# LTE_GPS_Power.net
KiCad netlist of a schematic drawn in Altium Designer
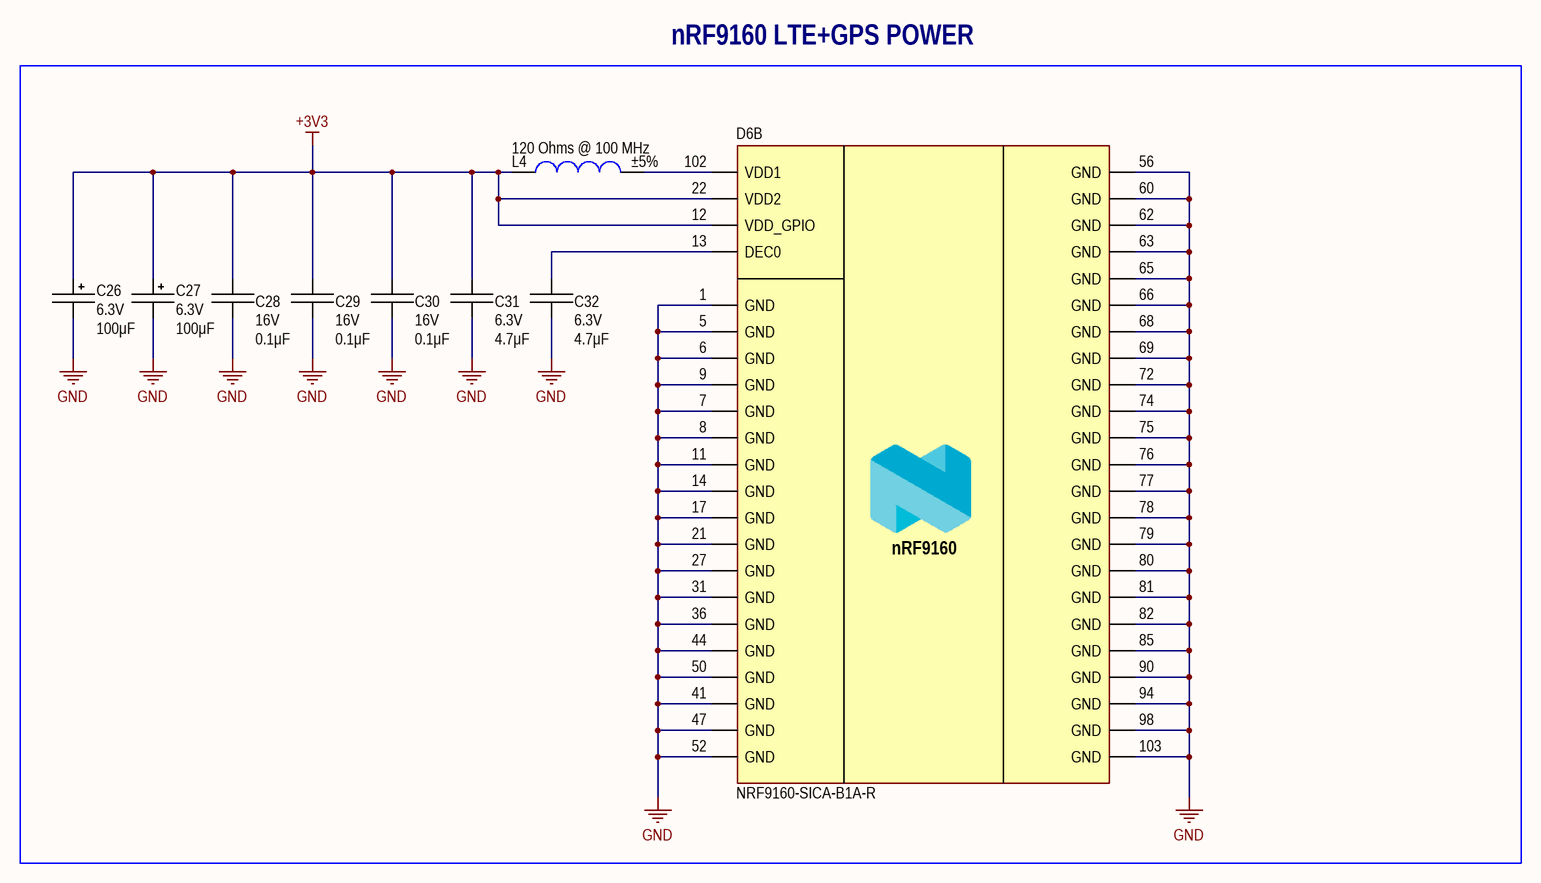
[diagram p0: LTE+GPS_Power.SchDoc]

(export (version "E")
  (design (tool "Eeschema 10.0.6"))
  (components
    (comp (ref "C26")
      (value "100μF")
      (footprint "CAP: TANTAL-A")
      (description "100 µF Molded Tantalum Polymer Capacitor 6.3 V 1206 (3216 Metric) 100mOhm @ 100kHz")
      (fields
        (field (name "MANUFACTURER") "AVX")
        (field (name "PARTNUMBER") "TCJA107M006R0100")
        (field (name "VOLTAGE") "6.3V")
      )
      (libsource (lib "capacitor") (part "Tantal_A"))
    )
    (comp (ref "C27")
      (value "100μF")
      (footprint "CAP: TANTAL-A")
      (description "100 µF Molded Tantalum Polymer Capacitor 6.3 V 1206 (3216 Metric) 100mOhm @ 100kHz")
      (fields
        (field (name "MANUFACTURER") "AVX")
        (field (name "PARTNUMBER") "TCJA107M006R0100")
        (field (name "VOLTAGE") "6.3V")
      )
      (libsource (lib "capacitor") (part "Tantal_A"))
    )
    (comp (ref "C28")
      (value "0.1μF")
      (footprint "CAP: 0402_NO_SILK")
      (description "0.1 µF ±10% 16V Ceramic Capacitor X7R 0402 (1005 Metric)")
      (fields
        (field (name "MANUFACTURER") "Yageo")
        (field (name "PARTNUMBER") "CC0402KRX7R7BB104")
        (field (name "VOLTAGE") "16V")
      )
      (libsource (lib "capacitor") (part "Ceramic_0402"))
    )
    (comp (ref "C29")
      (value "0.1μF")
      (footprint "CAP: 0402_NO_SILK")
      (description "0.1 µF ±10% 16V Ceramic Capacitor X7R 0402 (1005 Metric)")
      (fields
        (field (name "MANUFACTURER") "Yageo")
        (field (name "PARTNUMBER") "CC0402KRX7R7BB104")
        (field (name "VOLTAGE") "16V")
      )
      (libsource (lib "capacitor") (part "Ceramic_0402"))
    )
    (comp (ref "C30")
      (value "0.1μF")
      (footprint "CAP: 0402_NO_SILK")
      (description "0.1 µF ±10% 16V Ceramic Capacitor X7R 0402 (1005 Metric)")
      (fields
        (field (name "MANUFACTURER") "Yageo")
        (field (name "PARTNUMBER") "CC0402KRX7R7BB104")
        (field (name "VOLTAGE") "16V")
      )
      (libsource (lib "capacitor") (part "Ceramic_0402"))
    )
    (comp (ref "C31")
      (value "4.7μF")
      (footprint "CAP: 0603_NO_SILK")
      (description "4.7 µF ±20% 6.3V Ceramic Capacitor X7R 0603 (1608 Metric)")
      (fields
        (field (name "MANUFACTURER") "Yageo")
        (field (name "PARTNUMBER") "CC0603MRX7R5BB475")
        (field (name "VOLTAGE") "6.3V")
      )
      (libsource (lib "capacitor") (part "Ceramic_0603"))
    )
    (comp (ref "C32")
      (value "4.7μF")
      (footprint "CAP: 0603_NO_SILK")
      (description "4.7 µF ±20% 6.3V Ceramic Capacitor X7R 0603 (1608 Metric)")
      (fields
        (field (name "MANUFACTURER") "Yageo")
        (field (name "PARTNUMBER") "CC0603MRX7R5BB475")
        (field (name "VOLTAGE") "6.3V")
      )
      (libsource (lib "capacitor") (part "Ceramic_0603"))
    )
    (comp (ref "D6")
      (value "~")
      (footprint "MOD: NRF9160")
      (description "LTE/GSM module")
      (fields
        (field (name "MANUFACTURER") "Nordic Semiconductor")
        (field (name "VALUEMANUFACTURERPARTNUMBER") "LTE/GSM module, LTE-M/NB-IoT/GPS, 2.4GHz, , , , , 3...5.5V, -40...+85°C, 127-LGA")
        (field (name "PARTNUMBER") "NRF9160-SICA-B1A-R")
      )
      (libsource (lib "MyLib") (part "nRF9160"))
    )
    (comp (ref "L4")
      (value "120 Ohms @ 100 MHz")
      (footprint "IND: 0402")
      (description "120 Ohms @ 100 MHz 1 Power Line Ferrite Bead 0402 (1005 Metric) 2A 55mOhm")
      (fields
        (field (name "MANUFACTURER") "Murata Electronics")
        (field (name "PARTNUMBER") "BLM15PX121SN1D")
        (field (name "TOLERANCE") "±5%")
      )
      (libsource (lib "inductor") (part "Inductor_0402"))
    )
  )
  (nets
    (net (code "1") (name "+3V3") (class "Default")
      (node (ref "C26") (pin "1") (pinfunction "1_1") (pintype "passive"))
      (node (ref "C27") (pin "1") (pinfunction "1_1") (pintype "passive"))
      (node (ref "C28") (pin "2") (pinfunction "2_2") (pintype "passive"))
      (node (ref "C29") (pin "2") (pinfunction "2_2") (pintype "passive"))
      (node (ref "C30") (pin "2") (pinfunction "2_2") (pintype "passive"))
      (node (ref "C31") (pin "2") (pinfunction "2_2") (pintype "passive"))
      (node (ref "D6") (pin "12") (pinfunction "VDD_GPIO_12") (pintype "power_in"))
      (node (ref "D6") (pin "22") (pinfunction "VDD2_22") (pintype "power_in"))
      (node (ref "L4") (pin "2") (pinfunction "2_2") (pintype "passive"))
    )
    (net (code "2") (name "GND") (class "Default")
      (node (ref "C26") (pin "2") (pinfunction "2_2") (pintype "passive"))
      (node (ref "C27") (pin "2") (pinfunction "2_2") (pintype "passive"))
      (node (ref "C28") (pin "1") (pinfunction "1_1") (pintype "passive"))
      (node (ref "C29") (pin "1") (pinfunction "1_1") (pintype "passive"))
      (node (ref "C30") (pin "1") (pinfunction "1_1") (pintype "passive"))
      (node (ref "C31") (pin "1") (pinfunction "1_1") (pintype "passive"))
      (node (ref "C32") (pin "1") (pinfunction "1_1") (pintype "passive"))
      (node (ref "D6") (pin "1") (pinfunction "GND_1") (pintype "power_in"))
      (node (ref "D6") (pin "103") (pinfunction "GND_103") (pintype "power_in"))
      (node (ref "D6") (pin "11") (pinfunction "GND_11") (pintype "passive"))
      (node (ref "D6") (pin "14") (pinfunction "GND_14") (pintype "power_in"))
      (node (ref "D6") (pin "17") (pinfunction "GND_17") (pintype "power_in"))
      (node (ref "D6") (pin "21") (pinfunction "GND_21") (pintype "power_in"))
      (node (ref "D6") (pin "27") (pinfunction "GND_27") (pintype "power_in"))
      (node (ref "D6") (pin "31") (pinfunction "GND_31") (pintype "power_in"))
      (node (ref "D6") (pin "36") (pinfunction "GND_36") (pintype "power_in"))
      (node (ref "D6") (pin "41") (pinfunction "GND_41") (pintype "power_in"))
      (node (ref "D6") (pin "44") (pinfunction "GND_44") (pintype "power_in"))
      (node (ref "D6") (pin "47") (pinfunction "GND_47") (pintype "power_in"))
      (node (ref "D6") (pin "5") (pinfunction "GND_5") (pintype "power_in"))
      (node (ref "D6") (pin "50") (pinfunction "GND_50") (pintype "power_in"))
      (node (ref "D6") (pin "52") (pinfunction "GND_52") (pintype "power_in"))
      (node (ref "D6") (pin "56") (pinfunction "GND_56") (pintype "power_in"))
      (node (ref "D6") (pin "6") (pinfunction "GND_6") (pintype "passive"))
      (node (ref "D6") (pin "60") (pinfunction "GND_60") (pintype "power_in"))
      (node (ref "D6") (pin "62") (pinfunction "GND_62") (pintype "power_in"))
      (node (ref "D6") (pin "63") (pinfunction "GND_63") (pintype "power_in"))
      (node (ref "D6") (pin "65") (pinfunction "GND_65") (pintype "power_in"))
      (node (ref "D6") (pin "66") (pinfunction "GND_66") (pintype "power_in"))
      (node (ref "D6") (pin "68") (pinfunction "GND_68") (pintype "passive"))
      (node (ref "D6") (pin "69") (pinfunction "GND_69") (pintype "passive"))
      (node (ref "D6") (pin "7") (pinfunction "GND_7") (pintype "passive"))
      (node (ref "D6") (pin "72") (pinfunction "GND_72") (pintype "power_in"))
      (node (ref "D6") (pin "74") (pinfunction "GND_74") (pintype "power_in"))
      (node (ref "D6") (pin "75") (pinfunction "GND_75") (pintype "power_in"))
      (node (ref "D6") (pin "76") (pinfunction "GND_76") (pintype "power_in"))
      (node (ref "D6") (pin "77") (pinfunction "GND_77") (pintype "power_in"))
      (node (ref "D6") (pin "78") (pinfunction "GND_78") (pintype "power_in"))
      (node (ref "D6") (pin "79") (pinfunction "GND_79") (pintype "power_in"))
      (node (ref "D6") (pin "8") (pinfunction "GND_8") (pintype "passive"))
      (node (ref "D6") (pin "80") (pinfunction "GND_80") (pintype "power_in"))
      (node (ref "D6") (pin "81") (pinfunction "GND_81") (pintype "power_in"))
      (node (ref "D6") (pin "82") (pinfunction "GND_82") (pintype "power_in"))
      (node (ref "D6") (pin "85") (pinfunction "GND_85") (pintype "power_in"))
      (node (ref "D6") (pin "9") (pinfunction "GND_9") (pintype "power_in"))
      (node (ref "D6") (pin "90") (pinfunction "GND_90") (pintype "power_in"))
      (node (ref "D6") (pin "94") (pinfunction "GND_94") (pintype "power_in"))
      (node (ref "D6") (pin "98") (pinfunction "GND_98") (pintype "power_in"))
    )
    (net (code "3") (name "Net-(D6B-DEC0)") (class "Default")
      (node (ref "C32") (pin "2") (pinfunction "2_2") (pintype "passive"))
      (node (ref "D6") (pin "13") (pinfunction "DEC0_13") (pintype "power_in"))
    )
    (net (code "4") (name "Net-(D6B-VDD1)") (class "Default")
      (node (ref "D6") (pin "102") (pinfunction "VDD1_102") (pintype "power_in"))
      (node (ref "L4") (pin "1") (pinfunction "1_1") (pintype "passive"))
    )
  )
)
